# 1.net
KiCad netlist of a schematic drawn in EasyEDA Pro
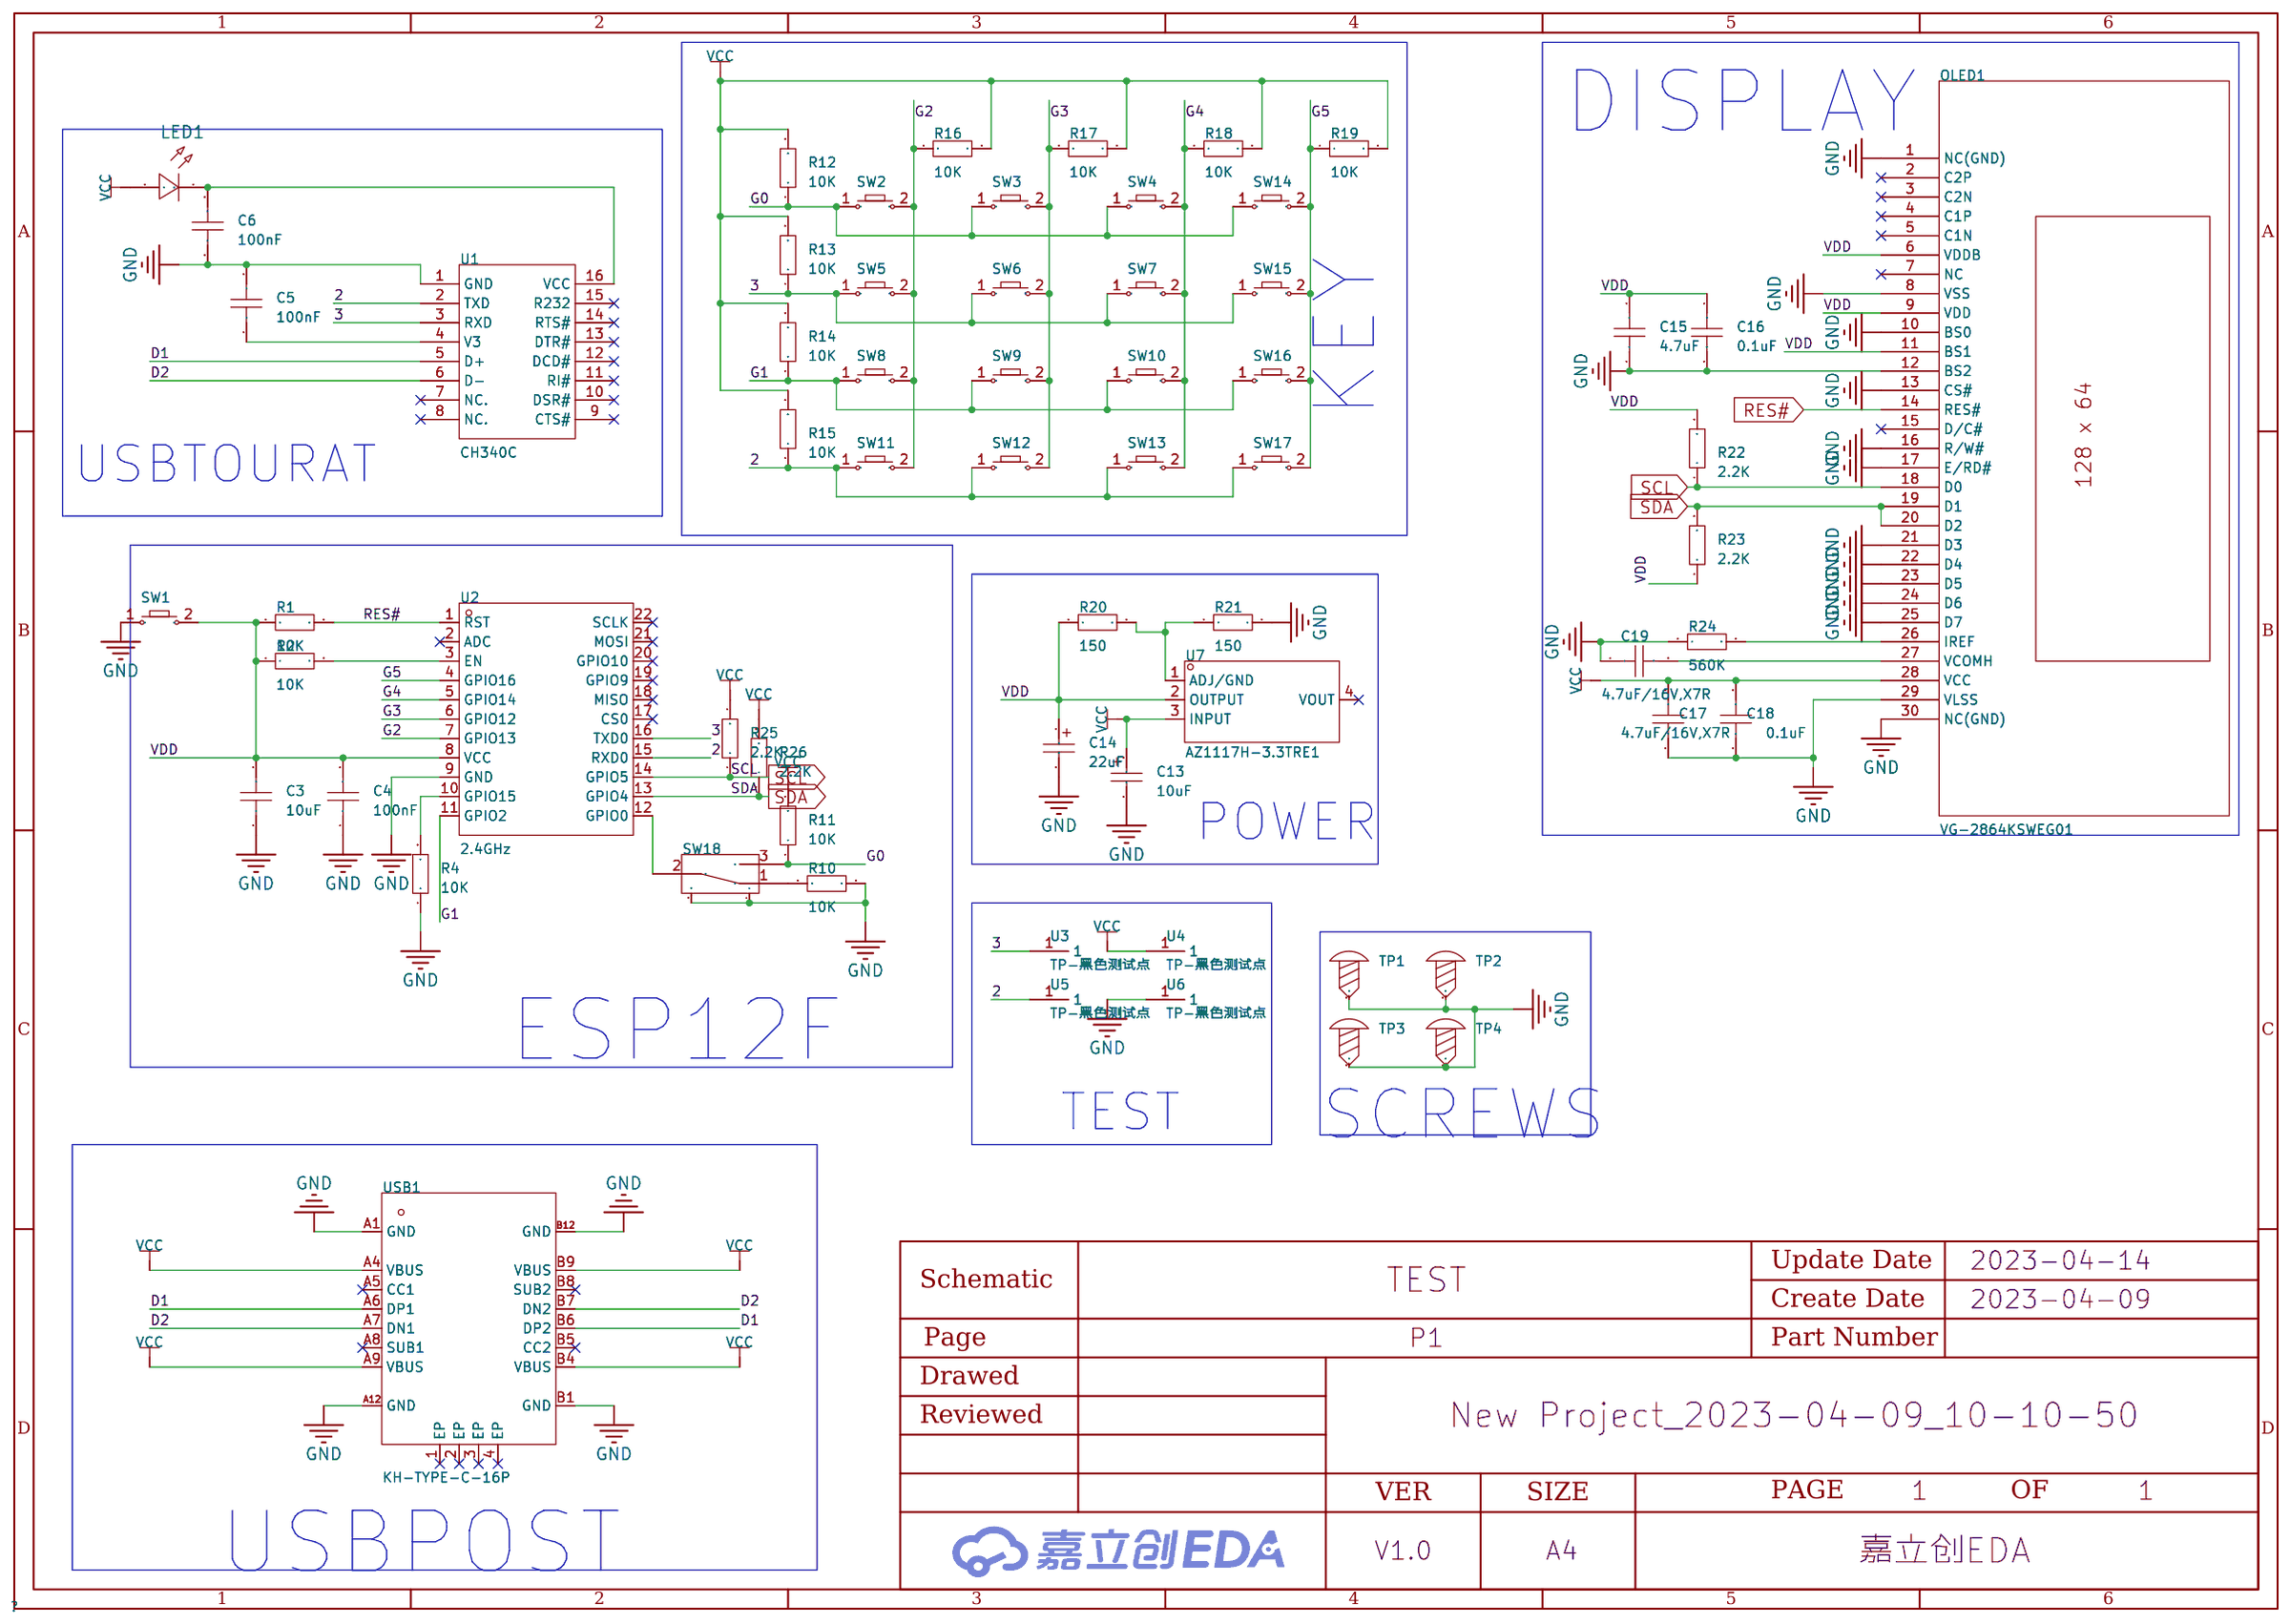
[diagram p0: schematic sheet]

(export (version "E")
  (design (tool "Eeschema 10.0.6"))
  (components
    (comp (ref "C3")
      (value "10uF")
      (footprint "easyedapro:C0603")
      (libsource (lib "easyedapro") (part "CapAcitance"))
    )
    (comp (ref "C4")
      (value "100nF")
      (footprint "easyedapro:C0603")
      (libsource (lib "easyedapro") (part "CapAcitance"))
    )
    (comp (ref "C5")
      (value "100nF")
      (footprint "easyedapro:C0603")
      (libsource (lib "easyedapro") (part "CapAcitance"))
    )
    (comp (ref "C6")
      (value "100nF")
      (footprint "easyedapro:C0603")
      (libsource (lib "easyedapro") (part "CapAcitance"))
    )
    (comp (ref "C13")
      (value "10uF")
      (footprint "easyedapro:CAP-SMD_L3.2-W1.6-RD-C7171")
      (description "容值:10uF;精度:±10%;额定电压:16V;等效串联电阻:3Ω@100kHz;")
      (fields (field (name "Manufacturer Part") "TAJA106K016RNJ") (field (name "Manufacturer") "Kyocera AVX"))
      (libsource (lib "easyedapro") (part "TAJA106K016RNJ"))
    )
    (comp (ref "C14")
      (value "22uF")
      (footprint "easyedapro:CASE-B_3528")
      (description "容值:22uF;精度:±10%;额定电压:16V;等效串联电阻:2.3Ω@100kHz;")
      (fields (field (name "Manufacturer Part") "TAJB226K016RNJ") (field (name "Manufacturer") "Kyocera AVX"))
      (libsource (lib "easyedapro") (part "TAJB226K016RNJ"))
    )
    (comp (ref "C15")
      (value "4.7uF")
      (footprint "easyedapro:C0603")
      (libsource (lib "easyedapro") (part "CapAcitance"))
    )
    (comp (ref "C16")
      (value "0.1uF")
      (footprint "easyedapro:C0603")
      (libsource (lib "easyedapro") (part "CapAcitance"))
    )
    (comp (ref "C17")
      (value "4.7uF/16V,X7R")
      (footprint "easyedapro:C0603")
      (libsource (lib "easyedapro") (part "CapAcitance"))
    )
    (comp (ref "C18")
      (value "0.1uF")
      (footprint "easyedapro:C0603")
      (libsource (lib "easyedapro") (part "CapAcitance"))
    )
    (comp (ref "C19")
      (value "4.7uF/16V,X7R")
      (footprint "easyedapro:C0603")
      (libsource (lib "easyedapro") (part "CapAcitance"))
    )
    (comp (ref "LED1")
      (value "~")
      (footprint "easyedapro:LED_0805")
      (libsource (lib "easyedapro") (part "LED_R"))
    )
    (comp (ref "OLED1")
      (value "VG-2864KSWEG01")
      (footprint "easyedapro:OLED_0.96-30P-P0.70-12864")
      (description "尺寸(inch):0.96;主控芯片:SSD1306;")
      (fields (field (name "Manufacturer") "WiseChip(智晶光电)"))
      (libsource (lib "easyedapro") (part "VG-2864KSWEG01"))
    )
    (comp (ref "R1") (value "10K") (footprint "easyedapro:R0603") (libsource (lib "easyedapro") (part "电阻")))
    (comp (ref "R2") (value "10K") (footprint "easyedapro:R0603") (libsource (lib "easyedapro") (part "电阻")))
    (comp (ref "R4") (value "10K") (footprint "easyedapro:R0603") (libsource (lib "easyedapro") (part "电阻")))
    (comp (ref "R10") (value "10K") (footprint "easyedapro:R0603") (libsource (lib "easyedapro") (part "电阻")))
    (comp (ref "R11") (value "10K") (footprint "easyedapro:R0603") (libsource (lib "easyedapro") (part "电阻")))
    (comp (ref "R12") (value "10K") (footprint "easyedapro:R0603") (libsource (lib "easyedapro") (part "电阻")))
    (comp (ref "R13") (value "10K") (footprint "easyedapro:R0603") (libsource (lib "easyedapro") (part "电阻")))
    (comp (ref "R14") (value "10K") (footprint "easyedapro:R0603") (libsource (lib "easyedapro") (part "电阻")))
    (comp (ref "R15") (value "10K") (footprint "easyedapro:R0603") (libsource (lib "easyedapro") (part "电阻")))
    (comp (ref "R16") (value "10K") (footprint "easyedapro:R0603") (libsource (lib "easyedapro") (part "电阻")))
    (comp (ref "R17") (value "10K") (footprint "easyedapro:R0603") (libsource (lib "easyedapro") (part "电阻")))
    (comp (ref "R18") (value "10K") (footprint "easyedapro:R0603") (libsource (lib "easyedapro") (part "电阻")))
    (comp (ref "R19") (value "10K") (footprint "easyedapro:R0603") (libsource (lib "easyedapro") (part "电阻")))
    (comp (ref "R20") (value "150") (footprint "easyedapro:R0603") (libsource (lib "easyedapro") (part "电阻")))
    (comp (ref "R21") (value "150") (footprint "easyedapro:R0603") (libsource (lib "easyedapro") (part "电阻")))
    (comp (ref "R22")
      (value "2.2K")
      (footprint "easyedapro:R0603")
      (libsource (lib "easyedapro") (part "电阻"))
    )
    (comp (ref "R23")
      (value "2.2K")
      (footprint "easyedapro:R0603")
      (libsource (lib "easyedapro") (part "电阻"))
    )
    (comp (ref "R24")
      (value "560K")
      (footprint "easyedapro:R0603")
      (libsource (lib "easyedapro") (part "电阻"))
    )
    (comp (ref "R25")
      (value "2.2K")
      (footprint "easyedapro:R0603")
      (libsource (lib "easyedapro") (part "电阻"))
    )
    (comp (ref "R26")
      (value "2.2K")
      (footprint "easyedapro:R0603")
      (libsource (lib "easyedapro") (part "电阻"))
    )
    (comp (ref "SW1")
      (value "~")
      (footprint "easyedapro:Key_SMD_3x4x2")
      (libsource (lib "easyedapro") (part "轻触按键x2"))
    )
    (comp (ref "SW2")
      (value "~")
      (footprint "easyedapro:Key_SMD_3x4x2")
      (libsource (lib "easyedapro") (part "轻触按键x2"))
    )
    (comp (ref "SW3")
      (value "~")
      (footprint "easyedapro:Key_SMD_3x4x2")
      (libsource (lib "easyedapro") (part "轻触按键x2"))
    )
    (comp (ref "SW4")
      (value "~")
      (footprint "easyedapro:Key_SMD_3x4x2")
      (libsource (lib "easyedapro") (part "轻触按键x2"))
    )
    (comp (ref "SW5")
      (value "~")
      (footprint "easyedapro:Key_SMD_3x4x2")
      (libsource (lib "easyedapro") (part "轻触按键x2"))
    )
    (comp (ref "SW6")
      (value "~")
      (footprint "easyedapro:Key_SMD_3x4x2")
      (libsource (lib "easyedapro") (part "轻触按键x2"))
    )
    (comp (ref "SW7")
      (value "~")
      (footprint "easyedapro:Key_SMD_3x4x2")
      (libsource (lib "easyedapro") (part "轻触按键x2"))
    )
    (comp (ref "SW8")
      (value "~")
      (footprint "easyedapro:Key_SMD_3x4x2")
      (libsource (lib "easyedapro") (part "轻触按键x2"))
    )
    (comp (ref "SW9")
      (value "~")
      (footprint "easyedapro:Key_SMD_3x4x2")
      (libsource (lib "easyedapro") (part "轻触按键x2"))
    )
    (comp (ref "SW10")
      (value "~")
      (footprint "easyedapro:Key_SMD_3x4x2")
      (libsource (lib "easyedapro") (part "轻触按键x2"))
    )
    (comp (ref "SW11")
      (value "~")
      (footprint "easyedapro:Key_SMD_3x4x2")
      (libsource (lib "easyedapro") (part "轻触按键x2"))
    )
    (comp (ref "SW12")
      (value "~")
      (footprint "easyedapro:Key_SMD_3x4x2")
      (libsource (lib "easyedapro") (part "轻触按键x2"))
    )
    (comp (ref "SW13")
      (value "~")
      (footprint "easyedapro:Key_SMD_3x4x2")
      (libsource (lib "easyedapro") (part "轻触按键x2"))
    )
    (comp (ref "SW14")
      (value "~")
      (footprint "easyedapro:Key_SMD_3x4x2")
      (libsource (lib "easyedapro") (part "轻触按键x2"))
    )
    (comp (ref "SW15")
      (value "~")
      (footprint "easyedapro:Key_SMD_3x4x2")
      (libsource (lib "easyedapro") (part "轻触按键x2"))
    )
    (comp (ref "SW16")
      (value "~")
      (footprint "easyedapro:Key_SMD_3x4x2")
      (libsource (lib "easyedapro") (part "轻触按键x2"))
    )
    (comp (ref "SW17")
      (value "~")
      (footprint "easyedapro:Key_SMD_3x4x2")
      (libsource (lib "easyedapro") (part "轻触按键x2"))
    )
    (comp (ref "SW18")
      (value "~")
      (footprint "easyedapro:拨动开关_侧")
      (libsource (lib "easyedapro") (part "拨动开关"))
    )
    (comp (ref "TP1") (value "~") (footprint "easyedapro:M2螺丝") (libsource (lib "easyedapro") (part "螺丝孔")))
    (comp (ref "TP2") (value "~") (footprint "easyedapro:M2螺丝") (libsource (lib "easyedapro") (part "螺丝孔")))
    (comp (ref "TP3") (value "~") (footprint "easyedapro:M2螺丝") (libsource (lib "easyedapro") (part "螺丝孔")))
    (comp (ref "TP4") (value "~") (footprint "easyedapro:M2螺丝") (libsource (lib "easyedapro") (part "螺丝孔")))
    (comp (ref "U1")
      (value "CH340C")
      (footprint "easyedapro:SOP-16_L10.0-W3.9-P1.27-LS6.0-BL")
      (description "驱动器/接收器数:-;协议类别:USB 2.0;类型:Transceiver;数据速率:2Mbps;")
      (fields (field (name "Manufacturer") "WCH(南京沁恒)"))
      (libsource (lib "easyedapro") (part "CH340C"))
    )
    (comp (ref "U2")
      (value "2.4GHz")
      (footprint "easyedapro:WIFIM-SMD_ESP-12F-ESP8266MOD")
      (description "频率:2.4GHz;发射功率:16dBm;核心处理器:ESP8266;天线形式:PCB 板载天线;接收灵敏度:-90dBm;")
      (fields
        (field (name "Manufacturer Part") "ESP-12F(ESP8266MOD)")
        (field (name "Manufacturer") "Ai-Thinker(安信可)")
      )
      (libsource (lib "easyedapro") (part "ESP-12F(ESP8266MOD)"))
    )
    (comp (ref "U3")
      (value "TP-黑色测试点")
      (footprint "easyedapro:TESTPOINT-TH_BD3.2")
      (libsource (lib "easyedapro") (part "TP-黑色测试点"))
    )
    (comp (ref "U4")
      (value "TP-黑色测试点")
      (footprint "easyedapro:TESTPOINT-TH_BD3.2")
      (libsource (lib "easyedapro") (part "TP-黑色测试点"))
    )
    (comp (ref "U5")
      (value "TP-黑色测试点")
      (footprint "easyedapro:TESTPOINT-TH_BD3.2")
      (libsource (lib "easyedapro") (part "TP-黑色测试点"))
    )
    (comp (ref "U6")
      (value "TP-黑色测试点")
      (footprint "easyedapro:TESTPOINT-TH_BD3.2")
      (libsource (lib "easyedapro") (part "TP-黑色测试点"))
    )
    (comp (ref "U7")
      (value "AZ1117H-3.3TRE1")
      (footprint "easyedapro:SOT-223-3_L6.5-W3.4-P2.30-LS7.0-BR")
      (description "最大输入电压:15V;压降(max):1.25V @ 1A;输出电压(可调):-;静态电流(Iq):-;输出类型:固定;输出电压(固定):3.3V;")
      (fields (field (name "Manufacturer") "DIODES(美台)"))
      (libsource (lib "easyedapro") (part "AZ1117H-3.3TRE1"))
    )
    (comp (ref "USB1")
      (value "KH-TYPE-C-16P")
      (footprint "easyedapro:USB-C-SMD_KH-TYPE-C-16P")
      (description "Type-C母座 16PIN 立式四角贴板无压片")
      (fields (field (name "Manufacturer") "kinghelm(金航标)"))
      (libsource (lib "easyedapro") (part "KH-TYPE-C-16P"))
    )
  )
  (nets
    (net (code "1") (name "/2") (class "Default")
      (node (ref "R15") (pin "1") (pinfunction "1_1") (pintype "input"))
      (node (ref "SW11") (pin "1") (pinfunction "1_1") (pintype "input"))
      (node (ref "SW12") (pin "1") (pinfunction "1_1") (pintype "input"))
      (node (ref "SW13") (pin "1") (pinfunction "1_1") (pintype "input"))
      (node (ref "SW17") (pin "1") (pinfunction "1_1") (pintype "input"))
      (node (ref "U1") (pin "2") (pinfunction "TXD_2") (pintype "input"))
      (node (ref "U2") (pin "15") (pinfunction "RXD0_15") (pintype "input"))
      (node (ref "U5") (pin "1") (pinfunction "1_1") (pintype "input"))
    )
    (net (code "2") (name "/3") (class "Default")
      (node (ref "R13") (pin "1") (pinfunction "1_1") (pintype "input"))
      (node (ref "SW15") (pin "1") (pinfunction "1_1") (pintype "input"))
      (node (ref "SW5") (pin "1") (pinfunction "1_1") (pintype "input"))
      (node (ref "SW6") (pin "1") (pinfunction "1_1") (pintype "input"))
      (node (ref "SW7") (pin "1") (pinfunction "1_1") (pintype "input"))
      (node (ref "U1") (pin "3") (pinfunction "RXD_3") (pintype "input"))
      (node (ref "U2") (pin "16") (pinfunction "TXD0_16") (pintype "input"))
      (node (ref "U3") (pin "1") (pinfunction "1_1") (pintype "input"))
    )
    (net (code "3") (name "/D1") (class "Default")
      (node (ref "U1") (pin "5") (pinfunction "D+_5") (pintype "input"))
      (node (ref "USB1") (pin "A6") (pinfunction "DP1_A6") (pintype "input"))
      (node (ref "USB1") (pin "B6") (pinfunction "DP2_B6") (pintype "input"))
    )
    (net (code "4") (name "/D2") (class "Default")
      (node (ref "U1") (pin "6") (pinfunction "D-_6") (pintype "input"))
      (node (ref "USB1") (pin "A7") (pinfunction "DN1_A7") (pintype "input"))
      (node (ref "USB1") (pin "B7") (pinfunction "DN2_B7") (pintype "input"))
    )
    (net (code "5") (name "/G0") (class "Default")
      (node (ref "R11") (pin "1") (pinfunction "1_1") (pintype "input"))
      (node (ref "R12") (pin "1") (pinfunction "1_1") (pintype "input"))
      (node (ref "SW14") (pin "1") (pinfunction "1_1") (pintype "input"))
      (node (ref "SW18") (pin "3") (pinfunction "3_3") (pintype "input"))
      (node (ref "SW2") (pin "1") (pinfunction "1_1") (pintype "input"))
      (node (ref "SW3") (pin "1") (pinfunction "1_1") (pintype "input"))
      (node (ref "SW4") (pin "1") (pinfunction "1_1") (pintype "input"))
    )
    (net (code "6") (name "/G1") (class "Default")
      (node (ref "R14") (pin "1") (pinfunction "1_1") (pintype "input"))
      (node (ref "SW10") (pin "1") (pinfunction "1_1") (pintype "input"))
      (node (ref "SW16") (pin "1") (pinfunction "1_1") (pintype "input"))
      (node (ref "SW8") (pin "1") (pinfunction "1_1") (pintype "input"))
      (node (ref "SW9") (pin "1") (pinfunction "1_1") (pintype "input"))
      (node (ref "U2") (pin "11") (pinfunction "GPIO2_11") (pintype "input"))
    )
    (net (code "7") (name "/G2") (class "Default")
      (node (ref "R16") (pin "1") (pinfunction "1_1") (pintype "input"))
      (node (ref "SW11") (pin "2") (pinfunction "2_2") (pintype "input"))
      (node (ref "SW2") (pin "2") (pinfunction "2_2") (pintype "input"))
      (node (ref "SW5") (pin "2") (pinfunction "2_2") (pintype "input"))
      (node (ref "SW8") (pin "2") (pinfunction "2_2") (pintype "input"))
      (node (ref "U2") (pin "7") (pinfunction "GPIO13_7") (pintype "input"))
    )
    (net (code "8") (name "/G3") (class "Default")
      (node (ref "R17") (pin "1") (pinfunction "1_1") (pintype "input"))
      (node (ref "SW12") (pin "2") (pinfunction "2_2") (pintype "input"))
      (node (ref "SW3") (pin "2") (pinfunction "2_2") (pintype "input"))
      (node (ref "SW6") (pin "2") (pinfunction "2_2") (pintype "input"))
      (node (ref "SW9") (pin "2") (pinfunction "2_2") (pintype "input"))
      (node (ref "U2") (pin "6") (pinfunction "GPIO12_6") (pintype "input"))
    )
    (net (code "9") (name "/G4") (class "Default")
      (node (ref "R18") (pin "1") (pinfunction "1_1") (pintype "input"))
      (node (ref "SW10") (pin "2") (pinfunction "2_2") (pintype "input"))
      (node (ref "SW13") (pin "2") (pinfunction "2_2") (pintype "input"))
      (node (ref "SW4") (pin "2") (pinfunction "2_2") (pintype "input"))
      (node (ref "SW7") (pin "2") (pinfunction "2_2") (pintype "input"))
      (node (ref "U2") (pin "5") (pinfunction "GPIO14_5") (pintype "input"))
    )
    (net (code "10") (name "/G5") (class "Default")
      (node (ref "R19") (pin "1") (pinfunction "1_1") (pintype "input"))
      (node (ref "SW14") (pin "2") (pinfunction "2_2") (pintype "input"))
      (node (ref "SW15") (pin "2") (pinfunction "2_2") (pintype "input"))
      (node (ref "SW16") (pin "2") (pinfunction "2_2") (pintype "input"))
      (node (ref "SW17") (pin "2") (pinfunction "2_2") (pintype "input"))
      (node (ref "U2") (pin "4") (pinfunction "GPIO16_4") (pintype "input"))
    )
    (net (code "11") (name "/VDD") (class "Default")
      (node (ref "C14") (pin "1") (pinfunction "1_1") (pintype "input"))
      (node (ref "C15") (pin "1") (pinfunction "1_1") (pintype "input"))
      (node (ref "C16") (pin "1") (pinfunction "1_1") (pintype "input"))
      (node (ref "C3") (pin "2") (pinfunction "2_2") (pintype "input"))
      (node (ref "C4") (pin "2") (pinfunction "2_2") (pintype "input"))
      (node (ref "OLED1") (pin "11") (pinfunction "BS1_11") (pintype "input"))
      (node (ref "OLED1") (pin "6") (pinfunction "VDDB_6") (pintype "input"))
      (node (ref "OLED1") (pin "9") (pinfunction "VDD_9") (pintype "input"))
      (node (ref "R1") (pin "1") (pinfunction "1_1") (pintype "input"))
      (node (ref "R2") (pin "1") (pinfunction "1_1") (pintype "input"))
      (node (ref "R20") (pin "1") (pinfunction "1_1") (pintype "input"))
      (node (ref "R22") (pin "2") (pinfunction "2_2") (pintype "input"))
      (node (ref "R23") (pin "1") (pinfunction "1_1") (pintype "input"))
      (node (ref "SW1") (pin "2") (pinfunction "2_2") (pintype "input"))
      (node (ref "U2") (pin "8") (pinfunction "VCC_8") (pintype "input"))
      (node (ref "U7") (pin "2") (pinfunction "OUTPUT_2") (pintype "input"))
    )
    (net (code "12") (name "GND") (class "Default")
      (node (ref "C13") (pin "2") (pinfunction "2_2") (pintype "input"))
      (node (ref "C14") (pin "2") (pinfunction "2_2") (pintype "input"))
      (node (ref "C15") (pin "2") (pinfunction "2_2") (pintype "input"))
      (node (ref "C16") (pin "2") (pinfunction "2_2") (pintype "input"))
      (node (ref "C17") (pin "1") (pinfunction "1_1") (pintype "input"))
      (node (ref "C18") (pin "1") (pinfunction "1_1") (pintype "input"))
      (node (ref "C19") (pin "1") (pinfunction "1_1") (pintype "input"))
      (node (ref "C3") (pin "1") (pinfunction "1_1") (pintype "input"))
      (node (ref "C4") (pin "1") (pinfunction "1_1") (pintype "input"))
      (node (ref "C5") (pin "2") (pinfunction "2_2") (pintype "input"))
      (node (ref "C6") (pin "1") (pinfunction "1_1") (pintype "input"))
      (node (ref "OLED1") (pin "1") (pinfunction "NC(GND)_1") (pintype "input"))
      (node (ref "OLED1") (pin "10") (pinfunction "BS0_10") (pintype "input"))
      (node (ref "OLED1") (pin "12") (pinfunction "BS2_12") (pintype "input"))
      (node (ref "OLED1") (pin "13") (pinfunction "CS#_13") (pintype "input"))
      (node (ref "OLED1") (pin "16") (pinfunction "R/W#_16") (pintype "input"))
      (node (ref "OLED1") (pin "17") (pinfunction "E/RD#_17") (pintype "input"))
      (node (ref "OLED1") (pin "21") (pinfunction "D3_21") (pintype "input"))
      (node (ref "OLED1") (pin "22") (pinfunction "D4_22") (pintype "input"))
      (node (ref "OLED1") (pin "23") (pinfunction "D5_23") (pintype "input"))
      (node (ref "OLED1") (pin "24") (pinfunction "D6_24") (pintype "input"))
      (node (ref "OLED1") (pin "25") (pinfunction "D7_25") (pintype "input"))
      (node (ref "OLED1") (pin "29") (pinfunction "VLSS_29") (pintype "input"))
      (node (ref "OLED1") (pin "30") (pinfunction "NC(GND)_30") (pintype "input"))
      (node (ref "OLED1") (pin "8") (pinfunction "VSS_8") (pintype "input"))
      (node (ref "R10") (pin "2") (pinfunction "2_2") (pintype "input"))
      (node (ref "R21") (pin "2") (pinfunction "2_2") (pintype "input"))
      (node (ref "R24") (pin "1") (pinfunction "1_1") (pintype "input"))
      (node (ref "R4") (pin "1") (pinfunction "1_1") (pintype "input"))
      (node (ref "SW1") (pin "1") (pinfunction "1_1") (pintype "input"))
      (node (ref "SW18") (pin "4") (pinfunction "4_4") (pintype "input"))
      (node (ref "SW18") (pin "5") (pinfunction "5_5") (pintype "input"))
      (node (ref "TP1") (pin "1") (pinfunction "1_1") (pintype "input"))
      (node (ref "TP2") (pin "1") (pinfunction "1_1") (pintype "input"))
      (node (ref "TP3") (pin "1") (pinfunction "1_1") (pintype "input"))
      (node (ref "TP4") (pin "1") (pinfunction "1_1") (pintype "input"))
      (node (ref "U1") (pin "1") (pinfunction "GND_1") (pintype "input"))
      (node (ref "U2") (pin "9") (pinfunction "GND_9") (pintype "input"))
      (node (ref "U6") (pin "1") (pinfunction "1_1") (pintype "input"))
      (node (ref "USB1") (pin "A1") (pinfunction "GND_A1") (pintype "input"))
      (node (ref "USB1") (pin "A12") (pinfunction "GND_A12") (pintype "input"))
      (node (ref "USB1") (pin "B1") (pinfunction "GND_B1") (pintype "input"))
      (node (ref "USB1") (pin "B12") (pinfunction "GND_B12") (pintype "input"))
    )
    (net (code "13") (name "Net-(LED1-C)") (class "Default")
      (node (ref "C6") (pin "2") (pinfunction "2_2") (pintype "input"))
      (node (ref "LED1") (pin "1") (pinfunction "C_1") (pintype "input"))
      (node (ref "U1") (pin "16") (pinfunction "VCC_16") (pintype "input"))
    )
    (net (code "14") (name "Net-(OLED1-IREF)") (class "Default")
      (node (ref "OLED1") (pin "26") (pinfunction "IREF_26") (pintype "input"))
      (node (ref "R24") (pin "2") (pinfunction "2_2") (pintype "input"))
    )
    (net (code "15") (name "Net-(OLED1-VCOMH)") (class "Default")
      (node (ref "C19") (pin "2") (pinfunction "2_2") (pintype "input"))
      (node (ref "OLED1") (pin "27") (pinfunction "VCOMH_27") (pintype "input"))
    )
    (net (code "16") (name "Net-(R10-Pad1)") (class "Default")
      (node (ref "R10") (pin "1") (pinfunction "1_1") (pintype "input"))
      (node (ref "SW18") (pin "1") (pinfunction "1_1") (pintype "input"))
    )
    (net (code "17") (name "Net-(U1-V3)") (class "Default")
      (node (ref "C5") (pin "1") (pinfunction "1_1") (pintype "input"))
      (node (ref "U1") (pin "4") (pinfunction "V3_4") (pintype "input"))
    )
    (net (code "18") (name "Net-(U2-EN)") (class "Default")
      (node (ref "R2") (pin "2") (pinfunction "2_2") (pintype "input"))
      (node (ref "U2") (pin "3") (pinfunction "EN_3") (pintype "input"))
    )
    (net (code "19") (name "Net-(U2-GPIO0)") (class "Default")
      (node (ref "SW18") (pin "2") (pinfunction "2_2") (pintype "input"))
      (node (ref "U2") (pin "12") (pinfunction "GPIO0_12") (pintype "input"))
    )
    (net (code "20") (name "Net-(U2-GPIO15)") (class "Default")
      (node (ref "R4") (pin "2") (pinfunction "2_2") (pintype "input"))
      (node (ref "U2") (pin "10") (pinfunction "GPIO15_10") (pintype "input"))
    )
    (net (code "21") (name "Net-(U7-ADJ{slash}GND)") (class "Default")
      (node (ref "R20") (pin "2") (pinfunction "2_2") (pintype "input"))
      (node (ref "R21") (pin "1") (pinfunction "1_1") (pintype "input"))
      (node (ref "U7") (pin "1") (pinfunction "ADJ/GND_1") (pintype "input"))
    )
    (net (code "22") (name "RES#") (class "Default")
      (node (ref "OLED1") (pin "14") (pinfunction "RES#_14") (pintype "input"))
      (node (ref "R1") (pin "2") (pinfunction "2_2") (pintype "input"))
      (node (ref "U2") (pin "1") (pinfunction "RST_1") (pintype "input"))
    )
    (net (code "23") (name "SCL") (class "Default")
      (node (ref "OLED1") (pin "18") (pinfunction "D0_18") (pintype "input"))
      (node (ref "R22") (pin "1") (pinfunction "1_1") (pintype "input"))
      (node (ref "R25") (pin "1") (pinfunction "1_1") (pintype "input"))
      (node (ref "U2") (pin "14") (pinfunction "GPIO5_14") (pintype "input"))
    )
    (net (code "24") (name "SDA") (class "Default")
      (node (ref "OLED1") (pin "19") (pinfunction "D1_19") (pintype "input"))
      (node (ref "OLED1") (pin "20") (pinfunction "D2_20") (pintype "input"))
      (node (ref "R23") (pin "2") (pinfunction "2_2") (pintype "input"))
      (node (ref "R26") (pin "1") (pinfunction "1_1") (pintype "input"))
      (node (ref "U2") (pin "13") (pinfunction "GPIO4_13") (pintype "input"))
    )
    (net (code "25") (name "VCC") (class "Default")
      (node (ref "C13") (pin "1") (pinfunction "1_1") (pintype "input"))
      (node (ref "C17") (pin "2") (pinfunction "2_2") (pintype "input"))
      (node (ref "C18") (pin "2") (pinfunction "2_2") (pintype "input"))
      (node (ref "LED1") (pin "2") (pinfunction "A_2") (pintype "input"))
      (node (ref "OLED1") (pin "28") (pinfunction "VCC_28") (pintype "input"))
      (node (ref "R11") (pin "2") (pinfunction "2_2") (pintype "input"))
      (node (ref "R12") (pin "2") (pinfunction "2_2") (pintype "input"))
      (node (ref "R13") (pin "2") (pinfunction "2_2") (pintype "input"))
      (node (ref "R14") (pin "2") (pinfunction "2_2") (pintype "input"))
      (node (ref "R15") (pin "2") (pinfunction "2_2") (pintype "input"))
      (node (ref "R16") (pin "2") (pinfunction "2_2") (pintype "input"))
      (node (ref "R17") (pin "2") (pinfunction "2_2") (pintype "input"))
      (node (ref "R18") (pin "2") (pinfunction "2_2") (pintype "input"))
      (node (ref "R19") (pin "2") (pinfunction "2_2") (pintype "input"))
      (node (ref "R25") (pin "2") (pinfunction "2_2") (pintype "input"))
      (node (ref "R26") (pin "2") (pinfunction "2_2") (pintype "input"))
      (node (ref "U4") (pin "1") (pinfunction "1_1") (pintype "input"))
      (node (ref "U7") (pin "3") (pinfunction "INPUT_3") (pintype "input"))
      (node (ref "USB1") (pin "A4") (pinfunction "VBUS_A4") (pintype "input"))
      (node (ref "USB1") (pin "A9") (pinfunction "VBUS_A9") (pintype "input"))
      (node (ref "USB1") (pin "B4") (pinfunction "VBUS_B4") (pintype "input"))
      (node (ref "USB1") (pin "B9") (pinfunction "VBUS_B9") (pintype "input"))
    )
    (net (code "26") (name "unconnected-(OLED1-C1N-Pad5)") (class "Default")
      (node (ref "OLED1") (pin "5") (pinfunction "C1N_5") (pintype "input+no_connect"))
    )
    (net (code "27") (name "unconnected-(OLED1-C1P-Pad4)") (class "Default")
      (node (ref "OLED1") (pin "4") (pinfunction "C1P_4") (pintype "input+no_connect"))
    )
    (net (code "28") (name "unconnected-(OLED1-C2N-Pad3)") (class "Default")
      (node (ref "OLED1") (pin "3") (pinfunction "C2N_3") (pintype "input+no_connect"))
    )
    (net (code "29") (name "unconnected-(OLED1-C2P-Pad2)") (class "Default")
      (node (ref "OLED1") (pin "2") (pinfunction "C2P_2") (pintype "input+no_connect"))
    )
    (net (code "30") (name "unconnected-(OLED1-D{slash}C#-Pad15)") (class "Default")
      (node (ref "OLED1") (pin "15") (pinfunction "D/C#_15") (pintype "input+no_connect"))
    )
    (net (code "31") (name "unconnected-(OLED1-NC-Pad7)") (class "Default")
      (node (ref "OLED1") (pin "7") (pinfunction "NC_7") (pintype "input+no_connect"))
    )
    (net (code "32") (name "unconnected-(U1-CTS#-Pad9)") (class "Default")
      (node (ref "U1") (pin "9") (pinfunction "CTS#_9") (pintype "input+no_connect"))
    )
    (net (code "33") (name "unconnected-(U1-DCD#-Pad12)") (class "Default")
      (node (ref "U1") (pin "12") (pinfunction "DCD#_12") (pintype "input+no_connect"))
    )
    (net (code "34") (name "unconnected-(U1-DSR#-Pad10)") (class "Default")
      (node (ref "U1") (pin "10") (pinfunction "DSR#_10") (pintype "input+no_connect"))
    )
    (net (code "35") (name "unconnected-(U1-DTR#-Pad13)") (class "Default")
      (node (ref "U1") (pin "13") (pinfunction "DTR#_13") (pintype "input+no_connect"))
    )
    (net (code "36") (name "unconnected-(U1-NC.-Pad7)") (class "Default")
      (node (ref "U1") (pin "7") (pinfunction "NC._7") (pintype "input+no_connect"))
    )
    (net (code "37") (name "unconnected-(U1-NC.-Pad8)") (class "Default")
      (node (ref "U1") (pin "8") (pinfunction "NC._8") (pintype "input+no_connect"))
    )
    (net (code "38") (name "unconnected-(U1-R232-Pad15)") (class "Default")
      (node (ref "U1") (pin "15") (pinfunction "R232_15") (pintype "input+no_connect"))
    )
    (net (code "39") (name "unconnected-(U1-RI#-Pad11)") (class "Default")
      (node (ref "U1") (pin "11") (pinfunction "RI#_11") (pintype "input+no_connect"))
    )
    (net (code "40") (name "unconnected-(U1-RTS#-Pad14)") (class "Default")
      (node (ref "U1") (pin "14") (pinfunction "RTS#_14") (pintype "input+no_connect"))
    )
    (net (code "41") (name "unconnected-(U2-ADC-Pad2)") (class "Default")
      (node (ref "U2") (pin "2") (pinfunction "ADC_2") (pintype "input+no_connect"))
    )
    (net (code "42") (name "unconnected-(U2-CS0-Pad17)") (class "Default")
      (node (ref "U2") (pin "17") (pinfunction "CS0_17") (pintype "input+no_connect"))
    )
    (net (code "43") (name "unconnected-(U2-GPIO9-Pad19)") (class "Default")
      (node (ref "U2") (pin "19") (pinfunction "GPIO9_19") (pintype "input+no_connect"))
    )
    (net (code "44") (name "unconnected-(U2-GPIO10-Pad20)") (class "Default")
      (node (ref "U2") (pin "20") (pinfunction "GPIO10_20") (pintype "input+no_connect"))
    )
    (net (code "45") (name "unconnected-(U2-MISO-Pad18)") (class "Default")
      (node (ref "U2") (pin "18") (pinfunction "MISO_18") (pintype "input+no_connect"))
    )
    (net (code "46") (name "unconnected-(U2-MOSI-Pad21)") (class "Default")
      (node (ref "U2") (pin "21") (pinfunction "MOSI_21") (pintype "input+no_connect"))
    )
    (net (code "47") (name "unconnected-(U2-SCLK-Pad22)") (class "Default")
      (node (ref "U2") (pin "22") (pinfunction "SCLK_22") (pintype "input+no_connect"))
    )
    (net (code "48") (name "unconnected-(U7-VOUT-Pad4)") (class "Default")
      (node (ref "U7") (pin "4") (pinfunction "VOUT_4") (pintype "input+no_connect"))
    )
    (net (code "49") (name "unconnected-(USB1-CC1-PadA5)") (class "Default")
      (node (ref "USB1") (pin "A5") (pinfunction "CC1_A5") (pintype "input+no_connect"))
    )
    (net (code "50") (name "unconnected-(USB1-CC2-PadB5)") (class "Default")
      (node (ref "USB1") (pin "B5") (pinfunction "CC2_B5") (pintype "input+no_connect"))
    )
    (net (code "51") (name "unconnected-(USB1-EP-Pad1)") (class "Default")
      (node (ref "USB1") (pin "1") (pinfunction "EP_1") (pintype "input+no_connect"))
    )
    (net (code "52") (name "unconnected-(USB1-EP-Pad2)") (class "Default")
      (node (ref "USB1") (pin "2") (pinfunction "EP_2") (pintype "input+no_connect"))
    )
    (net (code "53") (name "unconnected-(USB1-EP-Pad3)") (class "Default")
      (node (ref "USB1") (pin "3") (pinfunction "EP_3") (pintype "input+no_connect"))
    )
    (net (code "54") (name "unconnected-(USB1-EP-Pad4)") (class "Default")
      (node (ref "USB1") (pin "4") (pinfunction "EP_4") (pintype "input+no_connect"))
    )
    (net (code "55") (name "unconnected-(USB1-SUB1-PadA8)") (class "Default")
      (node (ref "USB1") (pin "A8") (pinfunction "SUB1_A8") (pintype "input+no_connect"))
    )
    (net (code "56") (name "unconnected-(USB1-SUB2-PadB8)") (class "Default")
      (node (ref "USB1") (pin "B8") (pinfunction "SUB2_B8") (pintype "input+no_connect"))
    )
  )
)
